# Police_Siren_using_Timer555.net
KiCad netlist of a schematic drawn in EAGLE
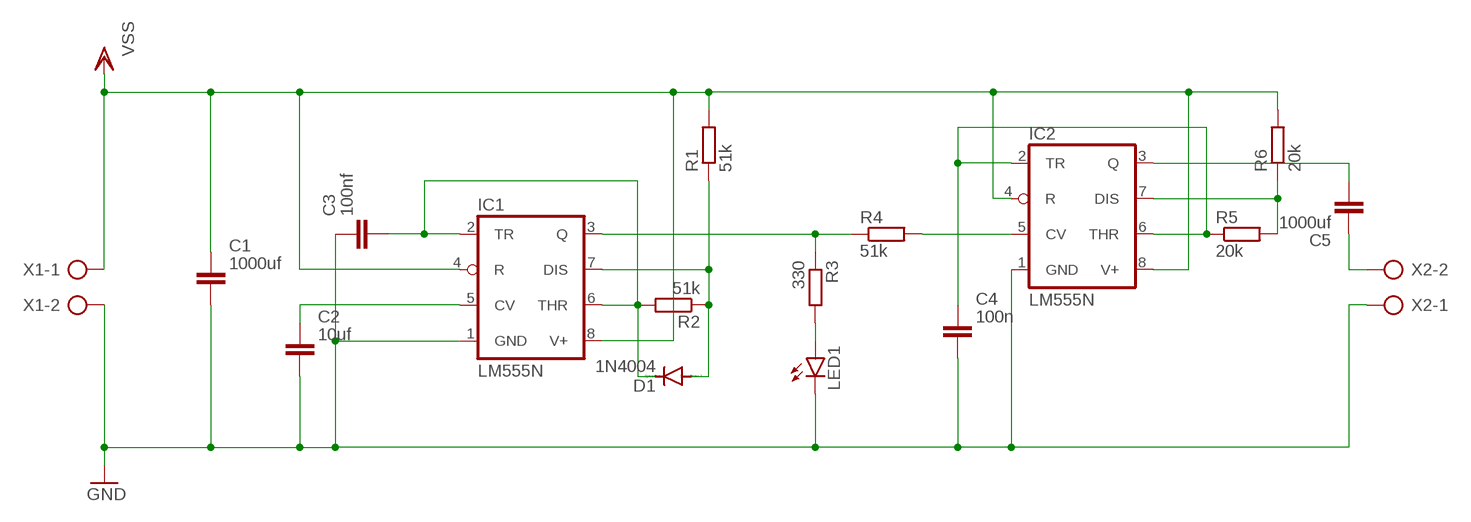
[diagram p0: schematic, sheet 1]

(export (version "E")
  (design (tool "Eeschema 10.0.6"))
  (components
    (comp (ref "C1")
      (value "1000uf")
      (footprint "eagle-import:CAPRD550W60D1025H1250B")
      (libsource (lib "eagle-import") (part "CRADIAL-12.5MM-DIA_"))
    )
    (comp (ref "C2")
      (value "10uf")
      (footprint "eagle-import:CAPRD550W60D1025H1250B")
      (libsource (lib "eagle-import") (part "CRADIAL-12.5MM-DIA_"))
    )
    (comp (ref "C3")
      (value "100nf")
      (footprint "eagle-import:CAPRD550W60D1025H1250B")
      (libsource (lib "eagle-import") (part "CRADIAL-12.5MM-DIA_"))
    )
    (comp (ref "C4")
      (value "100n")
      (footprint "eagle-import:CAPRD550W60D1025H1250B")
      (libsource (lib "eagle-import") (part "CRADIAL-12.5MM-DIA_"))
    )
    (comp (ref "C5")
      (value "1000uf")
      (footprint "eagle-import:CAPRD550W60D1025H1250B")
      (libsource (lib "eagle-import") (part "CRADIAL-12.5MM-DIA_"))
    )
    (comp (ref "D1")
      (value "1N4004")
      (footprint "eagle-import:DO41-10")
      (libsource (lib "eagle-import") (part "1N4004"))
    )
    (comp (ref "IC1")
      (value "LM555N")
      (footprint "eagle-import:DIL08")
      (libsource (lib "eagle-import") (part "555NLM"))
    )
    (comp (ref "IC2")
      (value "LM555N")
      (footprint "eagle-import:DIL08")
      (libsource (lib "eagle-import") (part "555NLM"))
    )
    (comp (ref "LED1")
      (value "LED3MM")
      (footprint "eagle-import:LED3MM")
      (libsource (lib "eagle-import") (part "LED3MM"))
    )
    (comp (ref "R1")
      (value "51k")
      (footprint "eagle-import:0204_7")
      (libsource (lib "eagle-import") (part "R-EU_0204/7"))
    )
    (comp (ref "R2")
      (value "51k")
      (footprint "eagle-import:0204_7")
      (libsource (lib "eagle-import") (part "R-EU_0204/7"))
    )
    (comp (ref "R3")
      (value "330")
      (footprint "eagle-import:0204_7")
      (libsource (lib "eagle-import") (part "R-EU_0204/7"))
    )
    (comp (ref "R4")
      (value "51k")
      (footprint "eagle-import:0204_7")
      (libsource (lib "eagle-import") (part "R-EU_0204/7"))
    )
    (comp (ref "R5")
      (value "20k")
      (footprint "eagle-import:0204_7")
      (libsource (lib "eagle-import") (part "R-EU_0204/7"))
    )
    (comp (ref "R6")
      (value "20k")
      (footprint "eagle-import:0204_7")
      (libsource (lib "eagle-import") (part "R-EU_0204/7"))
    )
    (comp (ref "X1")
      (value "AK300/2")
      (footprint "eagle-import:AK300_2")
      (libsource (lib "eagle-import") (part "AK300/2"))
    )
    (comp (ref "X2")
      (value "AK300/2")
      (footprint "eagle-import:AK300_2")
      (libsource (lib "eagle-import") (part "AK300/2"))
    )
  )
  (nets
    (net (code "1") (name "GND") (class "Default")
      (node (ref "C1") (pin "2") (pinfunction "2_2") (pintype "passive"))
      (node (ref "C2") (pin "2") (pinfunction "2_2") (pintype "passive"))
      (node (ref "C3") (pin "1") (pinfunction "1_1") (pintype "passive"))
      (node (ref "C4") (pin "2") (pinfunction "2_2") (pintype "passive"))
      (node (ref "IC1") (pin "1") (pinfunction "GND_1") (pintype "power_in"))
      (node (ref "IC2") (pin "1") (pinfunction "GND_1") (pintype "power_in"))
      (node (ref "LED1") (pin "K") (pinfunction "C_K") (pintype "passive"))
      (node (ref "X1") (pin "2") (pinfunction "KL_2") (pintype "passive"))
      (node (ref "X2") (pin "1") (pinfunction "KL_1") (pintype "passive"))
    )
    (net (code "2") (name "Net-(IC1-CV)") (class "Default")
      (node (ref "C2") (pin "1") (pinfunction "1_1") (pintype "passive"))
      (node (ref "IC1") (pin "5") (pinfunction "CV_5") (pintype "input"))
    )
    (net (code "3") (name "Net-(IC1-DIS)") (class "Default")
      (node (ref "D1") (pin "A") (pinfunction "A_A") (pintype "passive"))
      (node (ref "IC1") (pin "7") (pinfunction "DIS_7") (pintype "input"))
      (node (ref "R1") (pin "1") (pinfunction "1_1") (pintype "passive"))
      (node (ref "R2") (pin "1") (pinfunction "1_1") (pintype "passive"))
    )
    (net (code "4") (name "Net-(IC1-Q)") (class "Default")
      (node (ref "IC1") (pin "3") (pinfunction "Q_3") (pintype "output"))
      (node (ref "R3") (pin "1") (pinfunction "1_1") (pintype "passive"))
      (node (ref "R4") (pin "1") (pinfunction "1_1") (pintype "passive"))
    )
    (net (code "5") (name "Net-(IC1-THR)") (class "Default")
      (node (ref "C3") (pin "2") (pinfunction "2_2") (pintype "passive"))
      (node (ref "D1") (pin "C") (pinfunction "C_C") (pintype "passive"))
      (node (ref "IC1") (pin "2") (pinfunction "TR_2") (pintype "input"))
      (node (ref "IC1") (pin "6") (pinfunction "THR_6") (pintype "input"))
      (node (ref "R2") (pin "2") (pinfunction "2_2") (pintype "passive"))
    )
    (net (code "6") (name "Net-(IC2-CV)") (class "Default")
      (node (ref "IC2") (pin "5") (pinfunction "CV_5") (pintype "input"))
      (node (ref "R4") (pin "2") (pinfunction "2_2") (pintype "passive"))
    )
    (net (code "7") (name "Net-(IC2-DIS)") (class "Default")
      (node (ref "IC2") (pin "7") (pinfunction "DIS_7") (pintype "input"))
      (node (ref "R5") (pin "2") (pinfunction "2_2") (pintype "passive"))
      (node (ref "R6") (pin "1") (pinfunction "1_1") (pintype "passive"))
    )
    (net (code "8") (name "Net-(IC2-Q)") (class "Default")
      (node (ref "C5") (pin "2") (pinfunction "2_2") (pintype "passive"))
      (node (ref "IC2") (pin "3") (pinfunction "Q_3") (pintype "output"))
    )
    (net (code "9") (name "Net-(IC2-THR)") (class "Default")
      (node (ref "C4") (pin "1") (pinfunction "1_1") (pintype "passive"))
      (node (ref "IC2") (pin "2") (pinfunction "TR_2") (pintype "input"))
      (node (ref "IC2") (pin "6") (pinfunction "THR_6") (pintype "input"))
      (node (ref "R5") (pin "1") (pinfunction "1_1") (pintype "passive"))
    )
    (net (code "10") (name "Net-(LED1-PadA)") (class "Default")
      (node (ref "LED1") (pin "A") (pinfunction "A_A") (pintype "passive"))
      (node (ref "R3") (pin "2") (pinfunction "2_2") (pintype "passive"))
    )
    (net (code "11") (name "Net-(X2B-KL)") (class "Default")
      (node (ref "C5") (pin "1") (pinfunction "1_1") (pintype "passive"))
      (node (ref "X2") (pin "2") (pinfunction "KL_2") (pintype "passive"))
    )
    (net (code "12") (name "VSS") (class "Default")
      (node (ref "C1") (pin "1") (pinfunction "1_1") (pintype "passive"))
      (node (ref "IC1") (pin "4") (pinfunction "R_4") (pintype "input"))
      (node (ref "IC1") (pin "8") (pinfunction "V+_8") (pintype "power_in"))
      (node (ref "IC2") (pin "4") (pinfunction "R_4") (pintype "input"))
      (node (ref "IC2") (pin "8") (pinfunction "V+_8") (pintype "power_in"))
      (node (ref "R1") (pin "2") (pinfunction "2_2") (pintype "passive"))
      (node (ref "R6") (pin "2") (pinfunction "2_2") (pintype "passive"))
      (node (ref "X1") (pin "1") (pinfunction "KL_1") (pintype "passive"))
    )
  )
)
